# AutoReverse3.net
KiCad netlist of a schematic drawn in Altium Designer
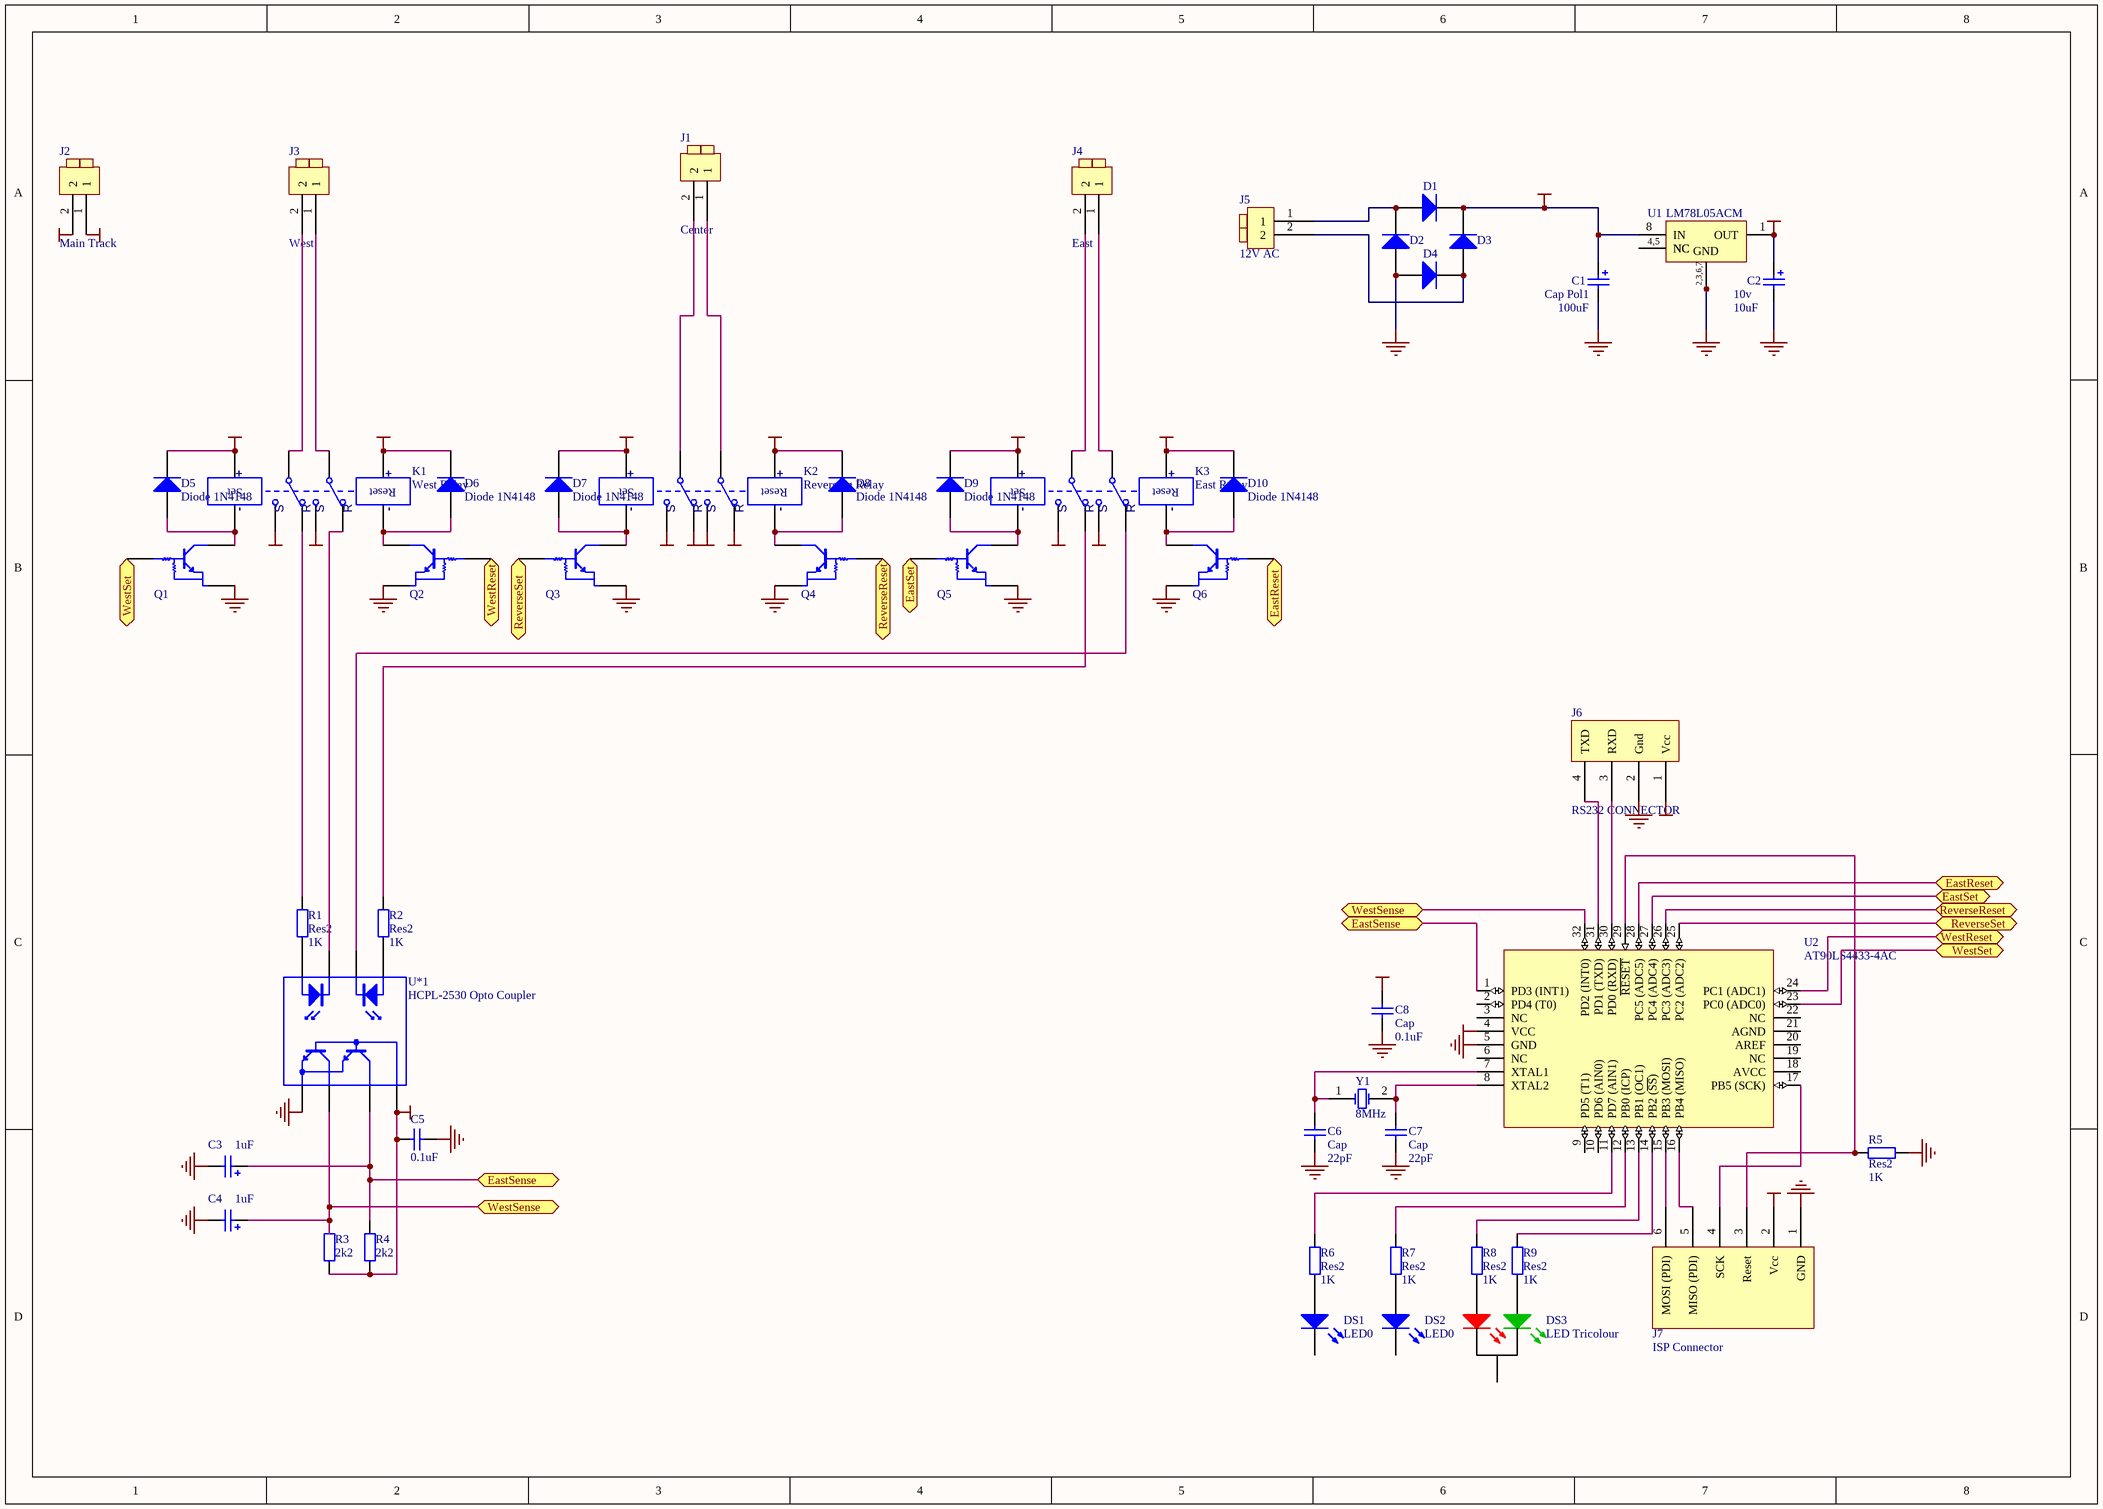
[diagram p0: AutoReverse3.SchDoc]

(export (version "E")
  (design (tool "Eeschema 10.0.6"))
  (components
    (comp (ref "C1")
      (value "Cap Pol1")
      (footprint "CAPPR5-10X10.5")
      (description "Polarized Capacitor (Radial)")
      (fields (field (name "ALTIUM_VALUE") "100uF") (field (name "PUBLISHER") "Altium Limited"))
      (libsource (lib "Miscellaneous Devices") (part "Cap Pol1"))
    )
    (comp (ref "C2")
      (value "10v")
      (footprint "CC3216-1206")
      (description "Polarized Capacitor (Radial)")
      (fields (field (name "ALTIUM_VALUE") "10uF") (field (name "PUBLISHER") "Altium Limited"))
      (libsource (lib "Miscellaneous Devices") (part "Cap Pol1"))
    )
    (comp (ref "C3")
      (value "1uF")
      (footprint "CC3216-1206")
      (description "Polarized Capacitor (Radial)")
      (fields (field (name "Comment") "Cap Pol1") (field (name "PUBLISHER") "Altium Limited"))
      (libsource (lib "Miscellaneous Devices") (part "Cap Pol1"))
    )
    (comp (ref "C4")
      (value "1uF")
      (footprint "CC3216-1206")
      (description "Polarized Capacitor (Radial)")
      (fields (field (name "Comment") "Cap Pol1") (field (name "PUBLISHER") "Altium Limited"))
      (libsource (lib "Miscellaneous Devices") (part "Cap Pol1"))
    )
    (comp (ref "C5")
      (value "0.1uF")
      (footprint "CC2012-0805")
      (description "Capacitor")
      (fields (field (name "Comment") "Cap") (field (name "PUBLISHER") "Altium Limited"))
      (libsource (lib "Miscellaneous Devices") (part "Cap"))
    )
    (comp (ref "C6")
      (value "Cap")
      (footprint "CC2012-0805")
      (description "Capacitor")
      (fields (field (name "ALTIUM_VALUE") "22pF") (field (name "PUBLISHER") "Altium Limited"))
      (libsource (lib "Miscellaneous Devices") (part "Cap"))
    )
    (comp (ref "C7")
      (value "Cap")
      (footprint "CC2012-0805")
      (description "Capacitor")
      (fields (field (name "ALTIUM_VALUE") "22pF") (field (name "PUBLISHER") "Altium Limited"))
      (libsource (lib "Miscellaneous Devices") (part "Cap"))
    )
    (comp (ref "C8")
      (value "Cap")
      (footprint "RAD-0.3")
      (description "Capacitor")
      (fields (field (name "ALTIUM_VALUE") "0.1uF") (field (name "PUBLISHER") "Altium Limited"))
      (libsource (lib "Miscellaneous Devices") (part "Cap"))
    )
    (comp (ref "D1")
      (value "Diode 1N4004")
      (footprint "DIO10.46-5.3x2.8")
      (description "1 Amp General Purpose Rectifier")
      (fields (field (name "PUBLISHER") "Altium Limited"))
      (libsource (lib "Miscellaneous Devices") (part "Diode 1N4004"))
    )
    (comp (ref "D2")
      (value "Diode 1N4004")
      (footprint "DIO10.46-5.3x2.8")
      (description "1 Amp General Purpose Rectifier")
      (fields (field (name "PUBLISHER") "Altium Limited"))
      (libsource (lib "Miscellaneous Devices") (part "Diode 1N4004"))
    )
    (comp (ref "D3")
      (value "Diode 1N4004")
      (footprint "DIO10.46-5.3x2.8")
      (description "1 Amp General Purpose Rectifier")
      (fields (field (name "PUBLISHER") "Altium Limited"))
      (libsource (lib "Miscellaneous Devices") (part "Diode 1N4004"))
    )
    (comp (ref "D4")
      (value "Diode 1N4004")
      (footprint "DIO10.46-5.3x2.8")
      (description "1 Amp General Purpose Rectifier")
      (fields (field (name "PUBLISHER") "Altium Limited"))
      (libsource (lib "Miscellaneous Devices") (part "Diode 1N4004"))
    )
    (comp (ref "D5")
      (value "Diode 1N4148")
      (footprint "DIO7.1-3.9x1.9")
      (description "High Conductance Fast Diode")
      (fields (field (name "PUBLISHER") "Altium Limited"))
      (libsource (lib "Miscellaneous Devices") (part "Diode 1N4148"))
    )
    (comp (ref "D6")
      (value "Diode 1N4148")
      (footprint "DIO7.1-3.9x1.9")
      (description "High Conductance Fast Diode")
      (fields (field (name "PUBLISHER") "Altium Limited"))
      (libsource (lib "Miscellaneous Devices") (part "Diode 1N4148"))
    )
    (comp (ref "D7")
      (value "Diode 1N4148")
      (footprint "DIO7.1-3.9x1.9")
      (description "High Conductance Fast Diode")
      (fields (field (name "PUBLISHER") "Altium Limited"))
      (libsource (lib "Miscellaneous Devices") (part "Diode 1N4148"))
    )
    (comp (ref "D8")
      (value "Diode 1N4148")
      (footprint "DIO7.1-3.9x1.9")
      (description "High Conductance Fast Diode")
      (fields (field (name "PUBLISHER") "Altium Limited"))
      (libsource (lib "Miscellaneous Devices") (part "Diode 1N4148"))
    )
    (comp (ref "D9")
      (value "Diode 1N4148")
      (footprint "DIO7.1-3.9x1.9")
      (description "High Conductance Fast Diode")
      (fields (field (name "PUBLISHER") "Altium Limited"))
      (libsource (lib "Miscellaneous Devices") (part "Diode 1N4148"))
    )
    (comp (ref "D10")
      (value "Diode 1N4148")
      (footprint "DIO7.1-3.9x1.9")
      (description "High Conductance Fast Diode")
      (fields (field (name "PUBLISHER") "Altium Limited"))
      (libsource (lib "Miscellaneous Devices") (part "Diode 1N4148"))
    )
    (comp (ref "DS1")
      (value "LED0")
      (footprint "LED-0")
      (description "Typical INFRARED GaAs LED")
      (fields (field (name "PUBLISHER") "Altium Limited"))
      (libsource (lib "Miscellaneous Devices") (part "LED0"))
    )
    (comp (ref "DS2")
      (value "LED0")
      (footprint "LED-0")
      (description "Typical INFRARED GaAs LED")
      (fields (field (name "PUBLISHER") "Altium Limited"))
      (libsource (lib "Miscellaneous Devices") (part "LED0"))
    )
    (comp (ref "DS3")
      (value "LED Tricolour")
      (footprint "LED3mm TriColour")
      (description "Typical Red Green Tri Color LED")
      (fields (field (name "PUBLISHER") "Altium Limited"))
      (libsource (lib "Custom") (part "LED Tricolour"))
    )
    (comp (ref "J1")
      (value "Center")
      (footprint "Screw Terminal 2 way 0.2")
      (libsource (lib "") (part "Screw Terminal 2 Way_1"))
    )
    (comp (ref "J2")
      (value "Main Track")
      (footprint "Screw Terminal 2 way 0.2")
      (libsource (lib "") (part "Screw Terminal 2 Way_1"))
    )
    (comp (ref "J3")
      (value "West")
      (footprint "Screw Terminal 2 way 0.2")
      (libsource (lib "") (part "Screw Terminal 2 Way_1"))
    )
    (comp (ref "J4")
      (value "East")
      (footprint "Screw Terminal 2 way 0.2")
      (libsource (lib "") (part "Screw Terminal 2 Way_1"))
    )
    (comp (ref "J5")
      (value "12V AC")
      (footprint "Screw Terminal 2 way 0.2")
      (libsource (lib "Custom") (part "Screw Terminal 2 Way"))
    )
    (comp (ref "J6")
      (value "RS232 CONNECTOR")
      (footprint "0.1 SIP 4 PIN")
      (libsource (lib "Custom") (part "RS232 CONNECTOR"))
    )
    (comp (ref "J7")
      (value "ISP Connector")
      (footprint "0.1 SIP 6 PIN")
      (libsource (lib "Custom") (part "ISP Connector"))
    )
    (comp (ref "K1")
      (value "West Relay")
      (footprint "DIP-10")
      (description "EA2-5T Dual Coil 5V Latching Relay")
      (fields (field (name "PUBLISHER") "Altium Limited"))
      (libsource (lib "Custom") (part "EA2-5T Dual Coil 5V Latching Relay"))
    )
    (comp (ref "K2")
      (value "Reversing Relay")
      (footprint "DIP-10")
      (description "EA2-5T Dual Coil 5V Latching Relay")
      (fields (field (name "PUBLISHER") "Altium Limited"))
      (libsource (lib "Custom") (part "EA2-5T Dual Coil 5V Latching Relay"))
    )
    (comp (ref "K3")
      (value "East Relay")
      (footprint "DIP-10")
      (description "EA2-5T Dual Coil 5V Latching Relay")
      (fields (field (name "PUBLISHER") "Altium Limited"))
      (libsource (lib "Custom") (part "EA2-5T Dual Coil 5V Latching Relay"))
    )
    (comp (ref "Q1")
      (value "UN2212")
      (footprint "SO-G3")
      (description "Bias Resistor Transistor")
      (libsource (lib "Custom") (part "UN2212"))
    )
    (comp (ref "Q2")
      (value "UN2212")
      (footprint "SO-G3")
      (description "Bias Resistor Transistor")
      (libsource (lib "Custom") (part "UN2212"))
    )
    (comp (ref "Q3")
      (value "UN2212")
      (footprint "SO-G3")
      (description "Bias Resistor Transistor")
      (libsource (lib "Custom") (part "UN2212"))
    )
    (comp (ref "Q4")
      (value "UN2212")
      (footprint "SO-G3")
      (description "Bias Resistor Transistor")
      (libsource (lib "Custom") (part "UN2212"))
    )
    (comp (ref "Q5")
      (value "UN2212")
      (footprint "SO-G3")
      (description "Bias Resistor Transistor")
      (libsource (lib "Custom") (part "UN2212"))
    )
    (comp (ref "Q6")
      (value "UN2212")
      (footprint "SO-G3")
      (description "Bias Resistor Transistor")
      (libsource (lib "Custom") (part "UN2212"))
    )
    (comp (ref "R1")
      (value "Res2")
      (footprint "AXIAL-0.4")
      (description "Resistor")
      (fields (field (name "ALTIUM_VALUE") "1K") (field (name "PUBLISHER") "Altium Limited"))
      (libsource (lib "Miscellaneous Devices") (part "Res2"))
    )
    (comp (ref "R2")
      (value "Res2")
      (footprint "AXIAL-0.4")
      (description "Resistor")
      (fields (field (name "ALTIUM_VALUE") "1K") (field (name "PUBLISHER") "Altium Limited"))
      (libsource (lib "Miscellaneous Devices") (part "Res2"))
    )
    (comp (ref "R3")
      (value "2k2")
      (footprint "CR2012-0805")
      (description "Resistor")
      (fields (field (name "Comment") "Res2") (field (name "PUBLISHER") "Altium Limited"))
      (libsource (lib "") (part "Res2_1"))
    )
    (comp (ref "R4")
      (value "2k2")
      (footprint "CR2012-0805")
      (description "Resistor")
      (fields (field (name "Comment") "Res2") (field (name "PUBLISHER") "Altium Limited"))
      (libsource (lib "") (part "Res2_1"))
    )
    (comp (ref "R5")
      (value "Res2")
      (footprint "AXIAL-0.4")
      (description "Resistor")
      (fields (field (name "ALTIUM_VALUE") "1K") (field (name "PUBLISHER") "Altium Limited"))
      (libsource (lib "") (part "Res2_2"))
    )
    (comp (ref "R6")
      (value "Res2")
      (footprint "AXIAL-0.4")
      (description "Resistor")
      (fields (field (name "ALTIUM_VALUE") "1K") (field (name "PUBLISHER") "Altium Limited"))
      (libsource (lib "Miscellaneous Devices") (part "Res2"))
    )
    (comp (ref "R7")
      (value "Res2")
      (footprint "AXIAL-0.4")
      (description "Resistor")
      (fields (field (name "ALTIUM_VALUE") "1K") (field (name "PUBLISHER") "Altium Limited"))
      (libsource (lib "Miscellaneous Devices") (part "Res2"))
    )
    (comp (ref "R8")
      (value "Res2")
      (footprint "AXIAL-0.4")
      (description "Resistor")
      (fields (field (name "ALTIUM_VALUE") "1K") (field (name "PUBLISHER") "Altium Limited"))
      (libsource (lib "Miscellaneous Devices") (part "Res2"))
    )
    (comp (ref "R9")
      (value "Res2")
      (footprint "AXIAL-0.4")
      (description "Resistor")
      (fields (field (name "ALTIUM_VALUE") "1K") (field (name "PUBLISHER") "Altium Limited"))
      (libsource (lib "Miscellaneous Devices") (part "Res2"))
    )
    (comp (ref "U*1")
      (value "HCPL-2530 Opto Coupler")
      (footprint "8P3")
      (libsource (lib "Custom") (part "HCPL-2530"))
    )
    (comp (ref "U1")
      (value "LM78L05ACM")
      (footprint "M08A")
      (description "3-Terminal Positive Regulator")
      (fields (field (name "PUBLISHER") "Altium Limited"))
      (libsource (lib "NSC Power Mgt Voltage Regulator") (part "LM78L05ACM"))
    )
    (comp (ref "U2")
      (value "AT90LS4433-4AC")
      (footprint "32A")
      (description "8-Bit AVR Microcontroller with 4K Bytes of In-System Programmable Flash Memory")
      (fields (field (name "PUBLISHER") "Altium Limited"))
      (libsource (lib "Custom") (part "AT90LS4433-4AC"))
    )
    (comp (ref "Y1")
      (value "8MHz")
      (footprint "BCY-W2/D3.1")
      (description "Crystal Oscillator")
      (fields (field (name "PUBLISHER") "Altium Limited"))
      (libsource (lib "Miscellaneous Devices") (part "XTAL"))
    )
  )
  (nets
    (net (code "1") (name "/EastReset") (class "Default")
      (node (ref "Q6") (pin "1") (pinfunction "B_1") (pintype "passive"))
      (node (ref "U2") (pin "28") (pinfunction "PC5_(ADC5)_28") (pintype "bidirectional"))
    )
    (net (code "2") (name "/EastSense") (class "Default")
      (node (ref "C3") (pin "1") (pinfunction "1_1") (pintype "passive"))
      (node (ref "R4") (pin "1") (pinfunction "1_1") (pintype "passive"))
      (node (ref "U*1") (pin "7") (pinfunction "C_7") (pintype "passive"))
      (node (ref "U2") (pin "1") (pinfunction "PD3_(INT1)_1") (pintype "bidirectional"))
    )
    (net (code "3") (name "/EastSet") (class "Default")
      (node (ref "Q5") (pin "1") (pinfunction "B_1") (pintype "passive"))
      (node (ref "U2") (pin "27") (pinfunction "PC4_(ADC4)_27") (pintype "bidirectional"))
    )
    (net (code "4") (name "/ReverseReset") (class "Default")
      (node (ref "Q4") (pin "1") (pinfunction "B_1") (pintype "passive"))
      (node (ref "U2") (pin "26") (pinfunction "PC3_(ADC3)_26") (pintype "bidirectional"))
    )
    (net (code "5") (name "/ReverseSet") (class "Default")
      (node (ref "Q3") (pin "1") (pinfunction "B_1") (pintype "passive"))
      (node (ref "U2") (pin "25") (pinfunction "PC2_(ADC2)_25") (pintype "bidirectional"))
    )
    (net (code "6") (name "/WestReset") (class "Default")
      (node (ref "Q2") (pin "1") (pinfunction "B_1") (pintype "passive"))
      (node (ref "U2") (pin "24") (pinfunction "PC1_(ADC1)_24") (pintype "bidirectional"))
    )
    (net (code "7") (name "/WestSense") (class "Default")
      (node (ref "C4") (pin "1") (pinfunction "1_1") (pintype "passive"))
      (node (ref "R3") (pin "1") (pinfunction "1_1") (pintype "passive"))
      (node (ref "U*1") (pin "6") (pinfunction "C_6") (pintype "passive"))
      (node (ref "U2") (pin "32") (pinfunction "PD2_(INT0)_32") (pintype "bidirectional"))
    )
    (net (code "8") (name "/WestSet") (class "Default")
      (node (ref "Q1") (pin "1") (pinfunction "B_1") (pintype "passive"))
      (node (ref "U2") (pin "23") (pinfunction "PC0_(ADC0)_23") (pintype "bidirectional"))
    )
    (net (code "9") (name "A") (class "Default")
      (node (ref "J2") (pin "2") (pinfunction "2_2") (pintype "passive"))
      (node (ref "K1") (pin "7") (pinfunction "S_7") (pintype "passive"))
      (node (ref "K2") (pin "2") (pinfunction "R_2") (pintype "passive"))
      (node (ref "K2") (pin "7") (pinfunction "S_7") (pintype "passive"))
      (node (ref "K3") (pin "7") (pinfunction "S_7") (pintype "passive"))
    )
    (net (code "10") (name "B") (class "Default")
      (node (ref "J2") (pin "1") (pinfunction "1_1") (pintype "passive"))
      (node (ref "K1") (pin "4") (pinfunction "S_4") (pintype "passive"))
      (node (ref "K2") (pin "4") (pinfunction "S_4") (pintype "passive"))
      (node (ref "K2") (pin "9") (pinfunction "R_9") (pintype "passive"))
      (node (ref "K3") (pin "4") (pinfunction "S_4") (pintype "passive"))
    )
    (net (code "11") (name "GND") (class "Default")
      (node (ref "C1") (pin "2") (pinfunction "2_2") (pintype "passive"))
      (node (ref "C2") (pin "2") (pinfunction "2_2") (pintype "passive"))
      (node (ref "C3") (pin "2") (pinfunction "2_2") (pintype "passive"))
      (node (ref "C4") (pin "2") (pinfunction "2_2") (pintype "passive"))
      (node (ref "C5") (pin "2") (pinfunction "2_2") (pintype "passive"))
      (node (ref "C6") (pin "1") (pinfunction "1_1") (pintype "passive"))
      (node (ref "C7") (pin "1") (pinfunction "1_1") (pintype "passive"))
      (node (ref "C8") (pin "1") (pinfunction "1_1") (pintype "passive"))
      (node (ref "D2") (pin "1") (pinfunction "A_1") (pintype "passive"))
      (node (ref "D4") (pin "1") (pinfunction "A_1") (pintype "passive"))
      (node (ref "J6") (pin "2") (pinfunction "Gnd_2") (pintype "passive"))
      (node (ref "J7") (pin "1") (pinfunction "GND_1") (pintype "passive"))
      (node (ref "Q1") (pin "2") (pinfunction "E_2") (pintype "passive"))
      (node (ref "Q2") (pin "2") (pinfunction "E_2") (pintype "passive"))
      (node (ref "Q3") (pin "2") (pinfunction "E_2") (pintype "passive"))
      (node (ref "Q4") (pin "2") (pinfunction "E_2") (pintype "passive"))
      (node (ref "Q5") (pin "2") (pinfunction "E_2") (pintype "passive"))
      (node (ref "Q6") (pin "2") (pinfunction "E_2") (pintype "passive"))
      (node (ref "R5") (pin "1") (pinfunction "1_1") (pintype "passive"))
      (node (ref "U*1") (pin "5") (pinfunction "E_5") (pintype "passive"))
      (node (ref "U1") (pin "2") (pinfunction "GND_2") (pintype "power_in"))
      (node (ref "U1") (pin "3") (pinfunction "GND_3") (pintype "power_in"))
      (node (ref "U1") (pin "6") (pinfunction "GND_6") (pintype "power_in"))
      (node (ref "U1") (pin "7") (pinfunction "GND_7") (pintype "power_in"))
      (node (ref "U2") (pin "5") (pinfunction "GND_5") (pintype "power_in"))
    )
    (net (code "12") (name "Net-(D1-A)") (class "Default")
      (node (ref "D1") (pin "1") (pinfunction "A_1") (pintype "passive"))
      (node (ref "D2") (pin "2") (pinfunction "K_2") (pintype "passive"))
      (node (ref "J5") (pin "1") (pinfunction "1_1") (pintype "passive"))
    )
    (net (code "13") (name "Net-(D3-A)") (class "Default")
      (node (ref "D3") (pin "1") (pinfunction "A_1") (pintype "passive"))
      (node (ref "D4") (pin "2") (pinfunction "K_2") (pintype "passive"))
      (node (ref "J5") (pin "2") (pinfunction "2_2") (pintype "passive"))
    )
    (net (code "14") (name "Net-(D5-A)") (class "Default")
      (node (ref "D5") (pin "1") (pinfunction "A_1") (pintype "passive"))
      (node (ref "K1") (pin "5") (pintype "passive"))
      (node (ref "Q1") (pin "3") (pinfunction "C_3") (pintype "passive"))
    )
    (net (code "15") (name "Net-(D6-A)") (class "Default")
      (node (ref "D6") (pin "1") (pinfunction "A_1") (pintype "passive"))
      (node (ref "K1") (pin "6") (pintype "passive"))
      (node (ref "Q2") (pin "3") (pinfunction "C_3") (pintype "passive"))
    )
    (net (code "16") (name "Net-(D7-A)") (class "Default")
      (node (ref "D7") (pin "1") (pinfunction "A_1") (pintype "passive"))
      (node (ref "K2") (pin "5") (pintype "passive"))
      (node (ref "Q3") (pin "3") (pinfunction "C_3") (pintype "passive"))
    )
    (net (code "17") (name "Net-(D8-A)") (class "Default")
      (node (ref "D8") (pin "1") (pinfunction "A_1") (pintype "passive"))
      (node (ref "K2") (pin "6") (pintype "passive"))
      (node (ref "Q4") (pin "3") (pinfunction "C_3") (pintype "passive"))
    )
    (net (code "18") (name "Net-(D9-A)") (class "Default")
      (node (ref "D9") (pin "1") (pinfunction "A_1") (pintype "passive"))
      (node (ref "K3") (pin "5") (pintype "passive"))
      (node (ref "Q5") (pin "3") (pinfunction "C_3") (pintype "passive"))
    )
    (net (code "19") (name "Net-(D10-A)") (class "Default")
      (node (ref "D10") (pin "1") (pinfunction "A_1") (pintype "passive"))
      (node (ref "K3") (pin "6") (pintype "passive"))
      (node (ref "Q6") (pin "3") (pinfunction "C_3") (pintype "passive"))
    )
    (net (code "20") (name "Net-(DS1-A)") (class "Default")
      (node (ref "DS1") (pin "1") (pinfunction "A_1") (pintype "passive"))
      (node (ref "R6") (pin "1") (pinfunction "1_1") (pintype "passive"))
    )
    (net (code "21") (name "Net-(DS2-A)") (class "Default")
      (node (ref "DS2") (pin "1") (pinfunction "A_1") (pintype "passive"))
      (node (ref "R7") (pin "1") (pinfunction "1_1") (pintype "passive"))
    )
    (net (code "22") (name "Net-(DS3-Ag)") (class "Default")
      (node (ref "DS3") (pin "1") (pinfunction "Ag_1") (pintype "passive"))
      (node (ref "R9") (pin "1") (pinfunction "1_1") (pintype "passive"))
    )
    (net (code "23") (name "Net-(DS3-Ar)") (class "Default")
      (node (ref "DS3") (pin "3") (pinfunction "Ar_3") (pintype "passive"))
      (node (ref "R8") (pin "1") (pinfunction "1_1") (pintype "passive"))
    )
    (net (code "24") (name "Net-(J1-Pad1)") (class "Default")
      (node (ref "J1") (pin "1") (pinfunction "1_1") (pintype "passive"))
      (node (ref "K2") (pin "3") (pinfunction "3_3") (pintype "passive"))
    )
    (net (code "25") (name "Net-(J1-Pad2)") (class "Default")
      (node (ref "J1") (pin "2") (pinfunction "2_2") (pintype "passive"))
      (node (ref "K2") (pin "8") (pinfunction "8_8") (pintype "passive"))
    )
    (net (code "26") (name "Net-(J3-Pad1)") (class "Default")
      (node (ref "J3") (pin "1") (pinfunction "1_1") (pintype "passive"))
      (node (ref "K1") (pin "3") (pinfunction "3_3") (pintype "passive"))
    )
    (net (code "27") (name "Net-(J3-Pad2)") (class "Default")
      (node (ref "J3") (pin "2") (pinfunction "2_2") (pintype "passive"))
      (node (ref "K1") (pin "8") (pinfunction "8_8") (pintype "passive"))
    )
    (net (code "28") (name "Net-(J4-Pad1)") (class "Default")
      (node (ref "J4") (pin "1") (pinfunction "1_1") (pintype "passive"))
      (node (ref "K3") (pin "3") (pinfunction "3_3") (pintype "passive"))
    )
    (net (code "29") (name "Net-(J4-Pad2)") (class "Default")
      (node (ref "J4") (pin "2") (pinfunction "2_2") (pintype "passive"))
      (node (ref "K3") (pin "8") (pinfunction "8_8") (pintype "passive"))
    )
    (net (code "30") (name "Net-(J6-RXD)") (class "Default")
      (node (ref "J6") (pin "3") (pinfunction "RXD_3") (pintype "passive"))
      (node (ref "U2") (pin "30") (pinfunction "PD0_(RXD)_30") (pintype "bidirectional"))
    )
    (net (code "31") (name "Net-(J6-TXD)") (class "Default")
      (node (ref "J6") (pin "4") (pinfunction "TXD_4") (pintype "passive"))
      (node (ref "U2") (pin "31") (pinfunction "PD1_(TXD)_31") (pintype "bidirectional"))
    )
    (net (code "32") (name "Net-(J7-MISO_(PDI))") (class "Default")
      (node (ref "J7") (pin "5") (pinfunction "MISO_(PDI)_5") (pintype "passive"))
      (node (ref "U2") (pin "16") (pinfunction "PB4_(MISO)_16") (pintype "bidirectional"))
    )
    (net (code "33") (name "Net-(J7-MOSI_(PDI))") (class "Default")
      (node (ref "J7") (pin "6") (pinfunction "MOSI_(PDI)_6") (pintype "passive"))
      (node (ref "U2") (pin "15") (pinfunction "PB3_(MOSI)_15") (pintype "bidirectional"))
    )
    (net (code "34") (name "Net-(J7-Reset)") (class "Default")
      (node (ref "J7") (pin "3") (pinfunction "Reset_3") (pintype "passive"))
      (node (ref "R5") (pin "2") (pinfunction "2_2") (pintype "passive"))
      (node (ref "U2") (pin "29") (pinfunction "~{RESET}_29") (pintype "input"))
    )
    (net (code "35") (name "Net-(J7-SCK)") (class "Default")
      (node (ref "J7") (pin "4") (pinfunction "SCK_4") (pintype "passive"))
      (node (ref "U2") (pin "17") (pinfunction "PB5_(SCK)_17") (pintype "bidirectional"))
    )
    (net (code "36") (name "Net-(K1-R-Pad2)") (class "Default")
      (node (ref "K1") (pin "2") (pinfunction "R_2") (pintype "passive"))
      (node (ref "U*1") (pin "3") (pinfunction "K_3") (pintype "passive"))
    )
    (net (code "37") (name "Net-(K1-R-Pad9)") (class "Default")
      (node (ref "K1") (pin "9") (pinfunction "R_9") (pintype "passive"))
      (node (ref "R1") (pin "2") (pinfunction "2_2") (pintype "passive"))
    )
    (net (code "38") (name "Net-(K3-R-Pad2)") (class "Default")
      (node (ref "K3") (pin "2") (pinfunction "R_2") (pintype "passive"))
      (node (ref "U*1") (pin "2") (pinfunction "K_2") (pintype "passive"))
    )
    (net (code "39") (name "Net-(K3-R-Pad9)") (class "Default")
      (node (ref "K3") (pin "9") (pinfunction "R_9") (pintype "passive"))
      (node (ref "R2") (pin "2") (pinfunction "2_2") (pintype "passive"))
    )
    (net (code "40") (name "Net-(R1-Pad1)") (class "Default")
      (node (ref "R1") (pin "1") (pinfunction "1_1") (pintype "passive"))
      (node (ref "U*1") (pin "4") (pinfunction "A_4") (pintype "passive"))
    )
    (net (code "41") (name "Net-(R2-Pad1)") (class "Default")
      (node (ref "R2") (pin "1") (pinfunction "1_1") (pintype "passive"))
      (node (ref "U*1") (pin "1") (pinfunction "A_1") (pintype "passive"))
    )
    (net (code "42") (name "Net-(U1-NC-Pad4)") (class "Default")
      (node (ref "U1") (pin "4") (pinfunction "NC_4") (pintype "passive"))
      (node (ref "U1") (pin "5") (pinfunction "NC_5") (pintype "passive"))
    )
    (net (code "43") (name "Net-(U2-PB0_(ICP))") (class "Default")
      (node (ref "R7") (pin "2") (pinfunction "2_2") (pintype "passive"))
      (node (ref "U2") (pin "12") (pinfunction "PB0_(ICP)_12") (pintype "bidirectional"))
    )
    (net (code "44") (name "Net-(U2-PB1_(OC1))") (class "Default")
      (node (ref "R8") (pin "2") (pinfunction "2_2") (pintype "passive"))
      (node (ref "U2") (pin "13") (pinfunction "PB1_(OC1)_13") (pintype "bidirectional"))
    )
    (net (code "45") (name "Net-(U2-PB2_(~{SS}))") (class "Default")
      (node (ref "R9") (pin "2") (pinfunction "2_2") (pintype "passive"))
      (node (ref "U2") (pin "14") (pinfunction "PB2_(~{SS})_14") (pintype "bidirectional"))
    )
    (net (code "46") (name "Net-(U2-PD7_(AIN1))") (class "Default")
      (node (ref "R6") (pin "2") (pinfunction "2_2") (pintype "passive"))
      (node (ref "U2") (pin "11") (pinfunction "PD7_(AIN1)_11") (pintype "bidirectional"))
    )
    (net (code "47") (name "Net-(U2-XTAL1)") (class "Default")
      (node (ref "C6") (pin "2") (pinfunction "2_2") (pintype "passive"))
      (node (ref "U2") (pin "7") (pinfunction "XTAL1_7") (pintype "passive"))
      (node (ref "Y1") (pin "1") (pinfunction "OSC1_1") (pintype "passive"))
    )
    (net (code "48") (name "Net-(U2-XTAL2)") (class "Default")
      (node (ref "C7") (pin "2") (pinfunction "2_2") (pintype "passive"))
      (node (ref "U2") (pin "8") (pinfunction "XTAL2_8") (pintype "passive"))
      (node (ref "Y1") (pin "2") (pinfunction "OSC2_2") (pintype "passive"))
    )
    (net (code "49") (name "VCC") (class "Default")
      (node (ref "C2") (pin "1") (pinfunction "1_1") (pintype "passive"))
      (node (ref "C5") (pin "1") (pinfunction "1_1") (pintype "passive"))
      (node (ref "C8") (pin "2") (pinfunction "2_2") (pintype "passive"))
      (node (ref "J6") (pin "1") (pinfunction "Vcc_1") (pintype "passive"))
      (node (ref "J7") (pin "2") (pinfunction "Vcc_2") (pintype "passive"))
      (node (ref "R3") (pin "2") (pinfunction "2_2") (pintype "passive"))
      (node (ref "R4") (pin "2") (pinfunction "2_2") (pintype "passive"))
      (node (ref "U*1") (pin "8") (pinfunction "E_8") (pintype "passive"))
      (node (ref "U1") (pin "1") (pinfunction "OUT_1") (pintype "power_in"))
      (node (ref "U2") (pin "4") (pinfunction "VCC_4") (pintype "power_in"))
    )
    (net (code "50") (name "Vdd") (class "Default")
      (node (ref "C1") (pin "1") (pinfunction "1_1") (pintype "passive"))
      (node (ref "D1") (pin "2") (pinfunction "K_2") (pintype "passive"))
      (node (ref "D10") (pin "2") (pinfunction "K_2") (pintype "passive"))
      (node (ref "D3") (pin "2") (pinfunction "K_2") (pintype "passive"))
      (node (ref "D5") (pin "2") (pinfunction "K_2") (pintype "passive"))
      (node (ref "D6") (pin "2") (pinfunction "K_2") (pintype "passive"))
      (node (ref "D7") (pin "2") (pinfunction "K_2") (pintype "passive"))
      (node (ref "D8") (pin "2") (pinfunction "K_2") (pintype "passive"))
      (node (ref "D9") (pin "2") (pinfunction "K_2") (pintype "passive"))
      (node (ref "K1") (pin "1") (pintype "passive"))
      (node (ref "K1") (pin "10") (pintype "passive"))
      (node (ref "K2") (pin "1") (pintype "passive"))
      (node (ref "K2") (pin "10") (pintype "passive"))
      (node (ref "K3") (pin "1") (pintype "passive"))
      (node (ref "K3") (pin "10") (pintype "passive"))
      (node (ref "U1") (pin "8") (pinfunction "IN_8") (pintype "power_in"))
    )
    (net (code "51") (name "unconnected-(DS1-K-Pad2)") (class "Default")
      (node (ref "DS1") (pin "2") (pinfunction "K_2") (pintype "passive"))
    )
    (net (code "52") (name "unconnected-(DS2-K-Pad2)") (class "Default")
      (node (ref "DS2") (pin "2") (pinfunction "K_2") (pintype "passive"))
    )
    (net (code "53") (name "unconnected-(DS3-K-Pad2)") (class "Default")
      (node (ref "DS3") (pin "2") (pinfunction "K_2") (pintype "passive"))
    )
    (net (code "54") (name "unconnected-(U2-AGND-Pad21)") (class "Default")
      (node (ref "U2") (pin "21") (pinfunction "AGND_21") (pintype "power_in"))
    )
    (net (code "55") (name "unconnected-(U2-AREF-Pad20)") (class "Default")
      (node (ref "U2") (pin "20") (pinfunction "AREF_20") (pintype "passive"))
    )
    (net (code "56") (name "unconnected-(U2-AVCC-Pad18)") (class "Default")
      (node (ref "U2") (pin "18") (pinfunction "AVCC_18") (pintype "power_in"))
    )
    (net (code "57") (name "unconnected-(U2-NC-Pad3)") (class "Default")
      (node (ref "U2") (pin "3") (pinfunction "NC_3") (pintype "passive"))
    )
    (net (code "58") (name "unconnected-(U2-NC-Pad6)") (class "Default")
      (node (ref "U2") (pin "6") (pinfunction "NC_6") (pintype "passive"))
    )
    (net (code "59") (name "unconnected-(U2-NC-Pad19)") (class "Default")
      (node (ref "U2") (pin "19") (pinfunction "NC_19") (pintype "passive"))
    )
    (net (code "60") (name "unconnected-(U2-NC-Pad22)") (class "Default")
      (node (ref "U2") (pin "22") (pinfunction "NC_22") (pintype "passive"))
    )
    (net (code "61") (name "unconnected-(U2-PD4_(T0)-Pad2)") (class "Default")
      (node (ref "U2") (pin "2") (pinfunction "PD4_(T0)_2") (pintype "bidirectional"))
    )
    (net (code "62") (name "unconnected-(U2-PD5_(T1)-Pad9)") (class "Default")
      (node (ref "U2") (pin "9") (pinfunction "PD5_(T1)_9") (pintype "bidirectional"))
    )
    (net (code "63") (name "unconnected-(U2-PD6_(AIN0)-Pad10)") (class "Default")
      (node (ref "U2") (pin "10") (pinfunction "PD6_(AIN0)_10") (pintype "bidirectional"))
    )
  )
)
